# ENABLE.net
KiCad netlist of a schematic drawn in Altium Designer
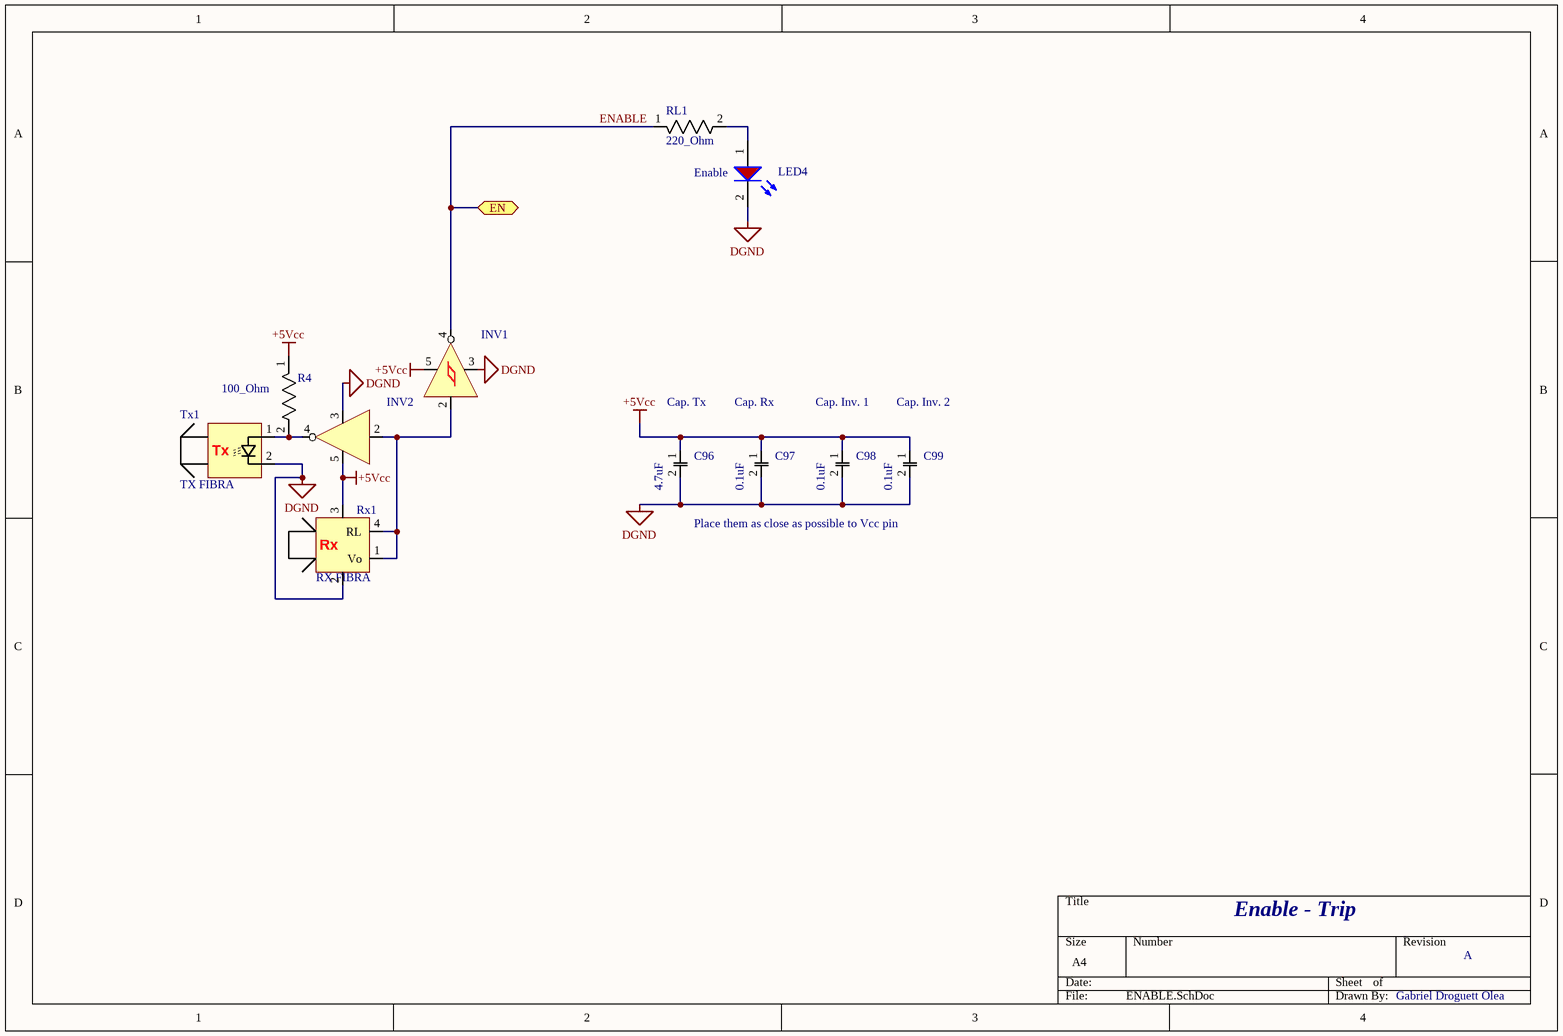
[diagram p0: ENABLE.SchDoc]

(export (version "E")
  (design (tool "Eeschema 10.0.6"))
  (components
    (comp (ref "C96")
      (value "4.7uF")
      (footprint "CAP_0603")
      (description "4.7µF ±20% 6.3V Ceramic Capacitor X5R 0603 (1608 Metric)")
      (fields
        (field (name "DIGI-KEY PART NUMBER") "732-7902-1-ND")
        (field (name "MANUFACTURER PART NUMBER") "885012106005")
      )
      (libsource (lib "CAP01uF_0603YC104KAT2A") (part "CAP_0603YC104KAT2A"))
    )
    (comp (ref "C97")
      (value "0.1uF")
      (footprint "CAP_0603")
      (description "0.1µF ±10% 16V Ceramic Capacitor X7R 0603 (1608 Metric)")
      (fields
        (field (name "DIGI-KEY PART NUMBER") "478-1239-1-ND")
        (field (name "MANUFACTURER PART NUMBER") "0603YC104KAT2A")
      )
      (libsource (lib "CAP01uF_0603YC104KAT2A") (part "CAP_0603YC104KAT2A"))
    )
    (comp (ref "C98")
      (value "0.1uF")
      (footprint "CAP_0603")
      (description "0.1µF ±10% 16V Ceramic Capacitor X7R 0603 (1608 Metric)")
      (fields
        (field (name "DIGI-KEY PART NUMBER") "478-1239-1-ND")
        (field (name "MANUFACTURER PART NUMBER") "0603YC104KAT2A")
      )
      (libsource (lib "CAP01uF_0603YC104KAT2A") (part "CAP_0603YC104KAT2A"))
    )
    (comp (ref "C99")
      (value "0.1uF")
      (footprint "CAP_0603")
      (description "0.1µF ±10% 16V Ceramic Capacitor X7R 0603 (1608 Metric)")
      (fields
        (field (name "DIGI-KEY PART NUMBER") "478-1239-1-ND")
        (field (name "MANUFACTURER PART NUMBER") "0603YC104KAT2A")
      )
      (libsource (lib "CAP01uF_0603YC104KAT2A") (part "CAP_0603YC104KAT2A"))
    )
    (comp (ref "INV1")
      (value "NOT SCHMITT")
      (footprint "INV_SN74AHC1G14DBVR")
      (description "IC SCHMITT-TRG INV GATE SOT23-5")
      (fields
        (field (name "DIGI-KEY PART NUMBER") "296-1092-1-ND")
        (field (name "MANUFACTURER PART NUMBER") "SN74AHC1G14DBVR")
      )
      (libsource (lib "INV_SN74AHC1G14DBVR") (part "INV_SN74AHC1G14DBVR"))
    )
    (comp (ref "INV2")
      (value "NOT OPEN COLLECTOR")
      (footprint "INV_SN74LVC1G06DBVR")
      (description "IC INVERTER SGL 1INPUT SOT23-5")
      (fields
        (field (name "DIGI-KEY PART NUMBER") "296-8483-1-ND")
        (field (name "MANUFACTURER PART NUMBER") "SN74LVC1G06DBVR")
      )
      (libsource (lib "INV_SN74LVC1G06DBVR") (part "INV_SN74LVC1G06DBVR"))
    )
    (comp (ref "LED4")
      (value "Enable")
      (footprint "LED_0805")
      (description "LED YELLOW CLEAR 0805 SMD")
      (fields
        (field (name "DIGI-KEY PART NUMBER") "732-4987-1-ND")
        (field (name "MANUFACTURER PART NUMBER") "150080YS75000")
      )
      (libsource (lib "WL-SMCW_rev15b") (part "WL-SMCW 0805  150080RS75000"))
    )
    (comp (ref "R4")
      (value "100_Ohm")
      (footprint "RES_0805")
      (description "RES 100 OHM 5% 1/4W 0805")
      (fields
        (field (name "DIGI-KEY PART NUMBER") "RPC0805JT100RCT-ND")
        (field (name "MANUFACTURER PART NUMBER") "RPC0805JT100R")
      )
      (libsource (lib "RES100_RPC0805JT100R") (part "RES100_RPC0805JT100R"))
    )
    (comp (ref "RL1")
      (value "220_Ohm")
      (footprint "res_0805")
      (description "1% 1/4W 0805")
      (fields
        (field (name "DIGI-KEY PART NUMBER") "311-220HRCT-ND")
        (field (name "MANUFACTURER PART NUMBER") "RC0603FR-07220RL")
      )
      (libsource (lib "RES470_ERJ-3GEYJ471V") (part "RES_ERJ-3GEYJ471V"))
    )
    (comp (ref "Rx1")
      (value "RX FIBRA")
      (footprint "Rx_HFBR-2521Z")
      (description "RECEIVER FIBER OPTIC 600NM 5MBD")
      (fields
        (field (name "DIGI-KEY PART NUMBER") "516-2062-ND")
        (field (name "MANUFACTURER PART NUMBER") "HFBR-2521Z")
      )
      (libsource (lib "Rx_HFBR-2521Z") (part "Rx_HFBR-2521Z"))
    )
    (comp (ref "Tx1")
      (value "TX FIBRA")
      (footprint "Tx_HFBR-1521Z")
      (description "XMITTER FIBER OPTIC 600NM 5MBD")
      (fields
        (field (name "DIGI-KEY PART NUMBER") "516-2043-ND")
        (field (name "MANUFACTURER PART NUMBER") "HFBR-1521Z")
      )
      (libsource (lib "Tx_HFBR-1521Z") (part "Tx_HFBR-1521Z"))
    )
  )
  (nets
    (net (code "1") (name "+5Vcc") (class "Default")
      (node (ref "C96") (pin "1") (pinfunction "1_1") (pintype "passive"))
      (node (ref "C97") (pin "1") (pinfunction "1_1") (pintype "passive"))
      (node (ref "C98") (pin "1") (pinfunction "1_1") (pintype "passive"))
      (node (ref "C99") (pin "1") (pinfunction "1_1") (pintype "passive"))
      (node (ref "INV1") (pin "5") (pinfunction "Vcc_5") (pintype "passive"))
      (node (ref "INV2") (pin "5") (pinfunction "Vcc_5") (pintype "passive"))
      (node (ref "R4") (pin "1") (pinfunction "C_1") (pintype "passive"))
      (node (ref "Rx1") (pin "3") (pinfunction "Vcc_3") (pintype "passive"))
    )
    (net (code "2") (name "/ENABLE") (class "Default")
      (node (ref "INV1") (pin "4") (pinfunction "Vcc_4") (pintype "passive"))
      (node (ref "RL1") (pin "1") (pinfunction "C_1") (pintype "passive"))
    )
    (net (code "3") (name "DGND") (class "Default")
      (node (ref "C96") (pin "2") (pinfunction "2_2") (pintype "passive"))
      (node (ref "C97") (pin "2") (pinfunction "2_2") (pintype "passive"))
      (node (ref "C98") (pin "2") (pinfunction "2_2") (pintype "passive"))
      (node (ref "C99") (pin "2") (pinfunction "2_2") (pintype "passive"))
      (node (ref "INV1") (pin "3") (pinfunction "GND_3") (pintype "passive"))
      (node (ref "INV2") (pin "3") (pinfunction "GND_3") (pintype "passive"))
      (node (ref "LED4") (pin "2") (pinfunction "C_2") (pintype "passive"))
      (node (ref "Rx1") (pin "2") (pinfunction "GND_2") (pintype "passive"))
      (node (ref "Tx1") (pin "2") (pinfunction "Catodo_2") (pintype "passive"))
    )
    (net (code "4") (name "Net-(INV1-A)") (class "Default")
      (node (ref "INV1") (pin "2") (pinfunction "A_2") (pintype "passive"))
      (node (ref "INV2") (pin "2") (pinfunction "A_2") (pintype "passive"))
      (node (ref "Rx1") (pin "1") (pinfunction "Vo_1") (pintype "passive"))
      (node (ref "Rx1") (pin "4") (pinfunction "RL_4") (pintype "passive"))
    )
    (net (code "5") (name "Net-(LED4-A)") (class "Default")
      (node (ref "LED4") (pin "1") (pinfunction "A_1") (pintype "passive"))
      (node (ref "RL1") (pin "2") (pinfunction "A_2") (pintype "passive"))
    )
    (net (code "6") (name "Net-(R4-A)") (class "Default")
      (node (ref "INV2") (pin "4") (pinfunction "Vcc_4") (pintype "passive"))
      (node (ref "R4") (pin "2") (pinfunction "A_2") (pintype "passive"))
      (node (ref "Tx1") (pin "1") (pinfunction "Anodo_1") (pintype "passive"))
    )
    (net (code "7") (name "unconnected-(INV1-NC-Pad1)") (class "Default")
      (node (ref "INV1") (pin "1") (pinfunction "NC_1") (pintype "passive"))
    )
    (net (code "8") (name "unconnected-(INV2-Pad1)") (class "Default")
      (node (ref "INV2") (pin "1") (pinfunction "1_1") (pintype "passive"))
    )
    (net (code "9") (name "unconnected-(Rx1-NC-Pad5)") (class "Default")
      (node (ref "Rx1") (pin "5") (pinfunction "NC_5") (pintype "passive"))
    )
    (net (code "10") (name "unconnected-(Rx1-NC-Pad8)") (class "Default")
      (node (ref "Rx1") (pin "8") (pinfunction "NC_8") (pintype "passive"))
    )
    (net (code "11") (name "unconnected-(Tx1-NC-Pad3)") (class "Default")
      (node (ref "Tx1") (pin "3") (pinfunction "NC_3") (pintype "passive"))
    )
    (net (code "12") (name "unconnected-(Tx1-NC-Pad4)") (class "Default")
      (node (ref "Tx1") (pin "4") (pinfunction "NC_4") (pintype "passive"))
    )
    (net (code "13") (name "unconnected-(Tx1-NC-Pad5)") (class "Default")
      (node (ref "Tx1") (pin "5") (pinfunction "NC_5") (pintype "passive"))
    )
    (net (code "14") (name "unconnected-(Tx1-NC-Pad8)") (class "Default")
      (node (ref "Tx1") (pin "8") (pinfunction "NC_8") (pintype "passive"))
    )
  )
)
